# SensWear_RGB.net
KiCad netlist of a schematic drawn in Altium Designer
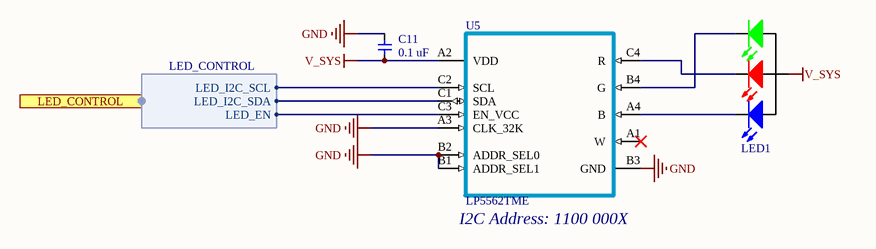
[diagram p0: SensWear_RGB.SchDoc]

(export (version "E")
  (design (tool "Eeschema 10.0.6"))
  (components
    (comp (ref "C11")
      (value "0.1 uF")
      (footprint "CAPC1005X05N")
      (description "CAP CER 0.1UF 16V X5R 0402")
      (fields
        (field (name "MANUFACTURER") "Murata Electronics")
        (field (name "MANUFACTURER PART NUMBER") "GRM155R61C104KA88D")
      )
      (libsource (lib "OpenRingComponents") (part "GRM155R61C104KA88D"))
    )
    (comp (ref "LED1")
      (value "SML-LX0404SIUPGUSB")
      (footprint "SML-LX0404SIUPGUSB")
      (description "LED Low-Power Tri-Color Blue/Green/Red 465nm/518nm/632nm 2.7V/2.75V/1.95V 4-Pin SMD T/R")
      (fields (field (name "MANUFACTURER") "Lumex"))
      (libsource (lib "OpenRingComponents") (part "SML-LX0404SIUPGUSB"))
    )
    (comp (ref "U5")
      (value "LP5562TME")
      (footprint "BGA12C40P4X3_162X122X68")
      (description "IC LED DRIVER LINEAR DIM 25.5MA")
      (fields
        (field (name "MANUFACTURER") "Texas Instruments")
        (field (name "MANUFACTURER PART NUMBER") "LP5562TME/NOPB")
      )
      (libsource (lib "OpenRingComponents") (part "LP5562TME/NOPB"))
    )
  )
  (nets
    (net (code "2") (name "/LED_EN") (class "Default")
      (node (ref "U5") (pin "C3") (pinfunction "EN_VCC_C3") (pintype "input"))
    )
    (net (code "3") (name "/LED_I2C_SCL") (class "Default")
      (node (ref "U5") (pin "C2") (pinfunction "SCL_C2") (pintype "input"))
    )
    (net (code "4") (name "/LED_I2C_SDA") (class "Default")
      (node (ref "U5") (pin "C1") (pinfunction "SDA_C1") (pintype "bidirectional"))
    )
    (net (code "6") (name "GND") (class "Default")
      (node (ref "C11") (pin "2") (pinfunction "2_2") (pintype "passive"))
      (node (ref "U5") (pin "A3") (pinfunction "CLK_32K_A3") (pintype "input"))
      (node (ref "U5") (pin "B1") (pinfunction "ADDR_SEL1_B1") (pintype "input"))
      (node (ref "U5") (pin "B2") (pinfunction "ADDR_SEL0_B2") (pintype "input"))
      (node (ref "U5") (pin "B3") (pinfunction "GND_B3") (pintype "power_in"))
    )
    (net (code "7") (name "Net-(U5-B)") (class "Default")
      (node (ref "LED1") (pin "3") (pinfunction "K_3") (pintype "passive"))
      (node (ref "U5") (pin "A4") (pinfunction "B_A4") (pintype "input"))
    )
    (net (code "8") (name "Net-(U5-G)") (class "Default")
      (node (ref "LED1") (pin "4") (pinfunction "K_4") (pintype "passive"))
      (node (ref "U5") (pin "B4") (pinfunction "G_B4") (pintype "input"))
    )
    (net (code "9") (name "Net-(U5-R)") (class "Default")
      (node (ref "LED1") (pin "2") (pinfunction "K_2") (pintype "passive"))
      (node (ref "U5") (pin "C4") (pinfunction "R_C4") (pintype "input"))
    )
    (net (code "10") (name "V_SYS") (class "Default")
      (node (ref "C11") (pin "1") (pinfunction "1_1") (pintype "passive"))
      (node (ref "LED1") (pin "1") (pinfunction "A_1") (pintype "passive"))
      (node (ref "U5") (pin "A2") (pinfunction "VDD_A2") (pintype "power_in"))
    )
    (net (code "11") (name "unconnected-(U5-W-PadA1)") (class "Default")
      (node (ref "U5") (pin "A1") (pinfunction "W_A1") (pintype "input+no_connect"))
    )
  )
)
